# ICSP-Breadboard-Adapter-ATMEGA328.net
KiCad netlist of a schematic drawn in EAGLE
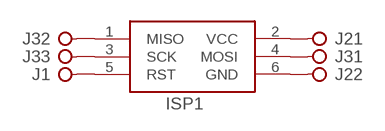
[diagram p0: schematic, sheet 1]

(export (version "E")
  (design (tool "Eeschema 10.0.6"))
  (components
    (comp (ref "ISP1")
      (value "ICSP-HEADER-6")
      (footprint "eagle-import:ICSP-HEADER")
      (libsource (lib "eagle-import") (part "ICSP-HEADER-6"))
    )
    (comp (ref "J1")
      (value "PINHD-1X1")
      (footprint "eagle-import:1X01")
      (libsource (lib "eagle-import") (part "PINHD-1X1"))
    )
    (comp (ref "J2")
      (value "PINHD-1X2")
      (footprint "eagle-import:1X02")
      (libsource (lib "eagle-import") (part "PINHD-1X2"))
    )
    (comp (ref "J3")
      (value "PINHD-1X3")
      (footprint "eagle-import:1X03")
      (libsource (lib "eagle-import") (part "PINHD-1X3"))
    )
  )
  (nets
    (net (code "1") (name "Net-(ISP1-GND)") (class "Default")
      (node (ref "ISP1") (pin "6") (pinfunction "GND_6") (pintype "power_in"))
      (node (ref "J2") (pin "2") (pinfunction "KL_2") (pintype "passive"))
    )
    (net (code "2") (name "Net-(ISP1-MISO)") (class "Default")
      (node (ref "ISP1") (pin "1") (pinfunction "MISO_1") (pintype "input"))
      (node (ref "J3") (pin "2") (pinfunction "KL_2") (pintype "passive"))
    )
    (net (code "3") (name "Net-(ISP1-MOSI)") (class "Default")
      (node (ref "ISP1") (pin "4") (pinfunction "MOSI_4") (pintype "output"))
      (node (ref "J3") (pin "1") (pinfunction "KL_1") (pintype "passive"))
    )
    (net (code "4") (name "Net-(ISP1-RST)") (class "Default")
      (node (ref "ISP1") (pin "5") (pinfunction "RST_5") (pintype "output"))
      (node (ref "J1") (pin "1") (pinfunction "KL_1") (pintype "passive"))
    )
    (net (code "5") (name "Net-(ISP1-SCK)") (class "Default")
      (node (ref "ISP1") (pin "3") (pinfunction "SCK_3") (pintype "output"))
      (node (ref "J3") (pin "3") (pinfunction "KL_3") (pintype "passive"))
    )
    (net (code "6") (name "Net-(ISP1-VCC)") (class "Default")
      (node (ref "ISP1") (pin "2") (pinfunction "VCC_2") (pintype "power_in"))
      (node (ref "J2") (pin "1") (pinfunction "KL_1") (pintype "passive"))
    )
  )
)
